# Analog_Signal_Conditioner_V2.net
KiCad netlist of a schematic drawn in Altium Designer
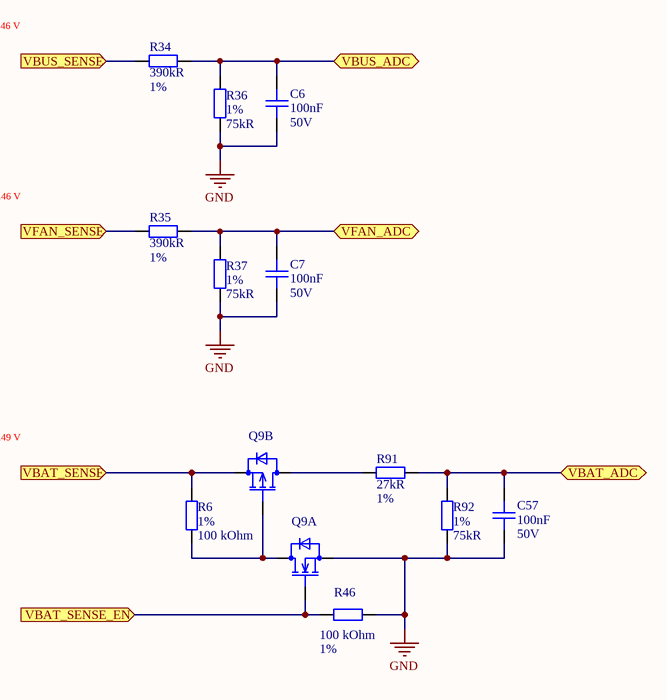
[diagram p0: Analog_Signal_Conditioner_V2.SchDoc]

(export (version "E")
  (design (tool "Eeschema 10.0.6"))
  (components
    (comp (ref "C6")
      (value "CAP CER 0.1UF 50V X7R 0402")
      (footprint "C0402")
      (description "0.1µF ±10% 50V Ceramic Capacitor X7R 0402 (1005 Metric)")
      (fields
        (field (name "MANUFACTURER PART NUMBER") "CGA2B3X7R1H104K050BB")
        (field (name "MANUFACTURER") "TDK")
        (field (name "CAPACITANCE") "100nF")
        (field (name "VOLTAGE") "50V")
      )
      (libsource (lib "capacitors_smd") (part "CAP CER 0.1UF 50V X7R 0402"))
    )
    (comp (ref "C7")
      (value "CAP CER 0.1UF 50V X7R 0402")
      (footprint "C0402")
      (description "0.1µF ±10% 50V Ceramic Capacitor X7R 0402 (1005 Metric)")
      (fields
        (field (name "MANUFACTURER PART NUMBER") "CGA2B3X7R1H104K050BB")
        (field (name "MANUFACTURER") "TDK")
        (field (name "CAPACITANCE") "100nF")
        (field (name "VOLTAGE") "50V")
      )
      (libsource (lib "capacitors_smd") (part "CAP CER 0.1UF 50V X7R 0402"))
    )
    (comp (ref "C57")
      (value "CAP CER 0.1UF 50V X7R 0402")
      (footprint "C0402")
      (description "0.1µF ±10% 50V Ceramic Capacitor X7R 0402 (1005 Metric)")
      (fields
        (field (name "MANUFACTURER PART NUMBER") "CGA2B3X7R1H104K050BB")
        (field (name "MANUFACTURER") "TDK")
        (field (name "CAPACITANCE") "100nF")
        (field (name "VOLTAGE") "50V")
      )
      (libsource (lib "capacitors_smd") (part "CAP CER 0.1UF 50V X7R 0402"))
    )
    (comp (ref "Q9")
      (value "EM6M2T2R")
      (footprint "SON_400UV-7_DIO")
      (description "Mosfet Array N and P-Channel 20V 200mA 150mW Surface Mount EMT6")
      (fields (field (name "MANUFACTURER") "Rohm"))
      (libsource (lib "mosfets") (part "ARRAY MOSFET N/P-CH 20V 0.2A EMT6"))
    )
    (comp (ref "R6")
      (value "RES SMD 100K OHM 1% 1/16W 0402")
      (footprint "R0402")
      (description "100 kOhms ±1% 0.063W, 1/16W Chip Resistor 0402 (1005 Metric) Moisture Resistant Thick Film")
      (fields
        (field (name "MANUFACTURER") "Yageo")
        (field (name "MANUFACTURER PART NUMBER") "RC0402FR-07100KL")
        (field (name "TOLERANCE") "1%")
        (field (name "RESISTANCE") "100 kOhm")
      )
      (libsource (lib "resistors_smd") (part "RES SMD 100K OHM 1% 1/16W 0402"))
    )
    (comp (ref "R34")
      (value "RES SMD 390K OHM 1% 1/16W 0402")
      (footprint "R0402")
      (description "390 kOhms ±1% 0.063W, 1/16W Chip Resistor 0402 (1005 Metric) Moisture Resistant Thick Film")
      (fields
        (field (name "MANUFACTURER") "Yageo")
        (field (name "MANUFACTURER PART NUMBER") "RC0402FR-07390KL")
        (field (name "RESISTANCE") "390kR")
        (field (name "TOLERANCE") "1%")
      )
      (libsource (lib "resistors_smd") (part "RES SMD 390K OHM 1% 1/16W 0402"))
    )
    (comp (ref "R35")
      (value "RES SMD 390K OHM 1% 1/16W 0402")
      (footprint "R0402")
      (description "390 kOhms ±1% 0.063W, 1/16W Chip Resistor 0402 (1005 Metric) Moisture Resistant Thick Film")
      (fields
        (field (name "MANUFACTURER") "Yageo")
        (field (name "MANUFACTURER PART NUMBER") "RC0402FR-07390KL")
        (field (name "RESISTANCE") "390kR")
        (field (name "TOLERANCE") "1%")
      )
      (libsource (lib "resistors_smd") (part "RES SMD 390K OHM 1% 1/16W 0402"))
    )
    (comp (ref "R36")
      (value "RES SMD 75K OHM 1% 1/16W 0402")
      (footprint "R0402")
      (description "75 kOhms ±1% 0.063W, 1/16W Chip Resistor 0402 (1005 Metric) Automotive AEC-Q200 Thick Film")
      (fields
        (field (name "MANUFACTURER") "Stackpole Electronics")
        (field (name "MANUFACTURER PART NUMBER") "RMCF0402FT75K0")
        (field (name "TOLERANCE") "1%")
        (field (name "RESISTANCE") "75kR")
      )
      (libsource (lib "resistors_smd") (part "RES SMD 75K OHM 1% 1/16W 0402"))
    )
    (comp (ref "R37")
      (value "RES SMD 75K OHM 1% 1/16W 0402")
      (footprint "R0402")
      (description "75 kOhms ±1% 0.063W, 1/16W Chip Resistor 0402 (1005 Metric) Automotive AEC-Q200 Thick Film")
      (fields
        (field (name "MANUFACTURER") "Stackpole Electronics")
        (field (name "MANUFACTURER PART NUMBER") "RMCF0402FT75K0")
        (field (name "TOLERANCE") "1%")
        (field (name "RESISTANCE") "75kR")
      )
      (libsource (lib "resistors_smd") (part "RES SMD 75K OHM 1% 1/16W 0402"))
    )
    (comp (ref "R46")
      (value "RES SMD 100K OHM 1% 1/16W 0402")
      (footprint "R0402")
      (description "100 kOhms ±1% 0.063W, 1/16W Chip Resistor 0402 (1005 Metric) Moisture Resistant Thick Film")
      (fields
        (field (name "MANUFACTURER") "Yageo")
        (field (name "MANUFACTURER PART NUMBER") "RC0402FR-07100KL")
        (field (name "TOLERANCE") "1%")
        (field (name "RESISTANCE") "100 kOhm")
      )
      (libsource (lib "") (part "RES SMD 100K OHM 1% 1/16W 0402_1"))
    )
    (comp (ref "R91")
      (value "RES SMD 27K OHM 1% 1/16W 0402")
      (footprint "R0402")
      (description "27 kOhms ±1% 0.063W, 1/16W Chip Resistor 0402 (1005 Metric) Moisture Resistant Thick Film")
      (fields
        (field (name "MANUFACTURER") "Yageo")
        (field (name "MANUFACTURER PART NUMBER") "RC0402FR-0727KL")
        (field (name "RESISTANCE") "27kR")
        (field (name "TOLERANCE") "1%")
      )
      (libsource (lib "resistors_smd") (part "RES SMD 27K OHM 1% 1/16W 0402"))
    )
    (comp (ref "R92")
      (value "RES SMD 75K OHM 1% 1/16W 0402")
      (footprint "R0402")
      (description "75 kOhms ±1% 0.063W, 1/16W Chip Resistor 0402 (1005 Metric) Automotive AEC-Q200 Thick Film")
      (fields
        (field (name "MANUFACTURER") "Stackpole Electronics")
        (field (name "MANUFACTURER PART NUMBER") "RMCF0402FT75K0")
        (field (name "TOLERANCE") "1%")
        (field (name "RESISTANCE") "75kR")
      )
      (libsource (lib "resistors_smd") (part "RES SMD 75K OHM 1% 1/16W 0402"))
    )
  )
  (nets
    (net (code "1") (name "/VBAT_ADC") (class "Default")
      (node (ref "C57") (pin "2") (pinfunction "2_2") (pintype "passive"))
      (node (ref "R91") (pin "2") (pinfunction "2_2") (pintype "passive"))
      (node (ref "R92") (pin "2") (pinfunction "2_2") (pintype "passive"))
    )
    (net (code "2") (name "/VBAT_SENSE") (class "Default")
      (node (ref "Q9") (pin "4") (pinfunction "S_4") (pintype "passive"))
      (node (ref "R6") (pin "2") (pinfunction "2_2") (pintype "passive"))
    )
    (net (code "3") (name "/VBAT_SENSE_EN") (class "Default")
      (node (ref "Q9") (pin "2") (pinfunction "G_2") (pintype "passive"))
      (node (ref "R46") (pin "2") (pinfunction "2_2") (pintype "passive"))
    )
    (net (code "4") (name "/VBUS_ADC") (class "Default")
      (node (ref "C6") (pin "2") (pinfunction "2_2") (pintype "passive"))
      (node (ref "R34") (pin "2") (pinfunction "2_2") (pintype "passive"))
      (node (ref "R36") (pin "2") (pinfunction "2_2") (pintype "passive"))
    )
    (net (code "5") (name "/VBUS_SENSE") (class "Default")
      (node (ref "R34") (pin "1") (pinfunction "1_1") (pintype "passive"))
    )
    (net (code "6") (name "/VFAN_ADC") (class "Default")
      (node (ref "C7") (pin "2") (pinfunction "2_2") (pintype "passive"))
      (node (ref "R35") (pin "2") (pinfunction "2_2") (pintype "passive"))
      (node (ref "R37") (pin "2") (pinfunction "2_2") (pintype "passive"))
    )
    (net (code "7") (name "/VFAN_SENSE") (class "Default")
      (node (ref "R35") (pin "1") (pinfunction "1_1") (pintype "passive"))
    )
    (net (code "8") (name "GND") (class "Default")
      (node (ref "C57") (pin "1") (pinfunction "1_1") (pintype "passive"))
      (node (ref "C6") (pin "1") (pinfunction "1_1") (pintype "passive"))
      (node (ref "C7") (pin "1") (pinfunction "1_1") (pintype "passive"))
      (node (ref "Q9") (pin "1") (pinfunction "S_1") (pintype "passive"))
      (node (ref "R36") (pin "1") (pinfunction "1_1") (pintype "passive"))
      (node (ref "R37") (pin "1") (pinfunction "1_1") (pintype "passive"))
      (node (ref "R46") (pin "1") (pinfunction "1_1") (pintype "passive"))
      (node (ref "R92") (pin "1") (pinfunction "1_1") (pintype "passive"))
    )
    (net (code "9") (name "Net-(Q9A-D)") (class "Default")
      (node (ref "Q9") (pin "5") (pinfunction "G_5") (pintype "passive"))
      (node (ref "Q9") (pin "6") (pinfunction "D_6") (pintype "passive"))
      (node (ref "R6") (pin "1") (pinfunction "1_1") (pintype "passive"))
    )
    (net (code "10") (name "Net-(Q9B-D)") (class "Default")
      (node (ref "Q9") (pin "3") (pinfunction "D_3") (pintype "passive"))
      (node (ref "R91") (pin "1") (pinfunction "1_1") (pintype "passive"))
    )
  )
)
